# untitled.net
KiCad netlist of a schematic drawn in EAGLE
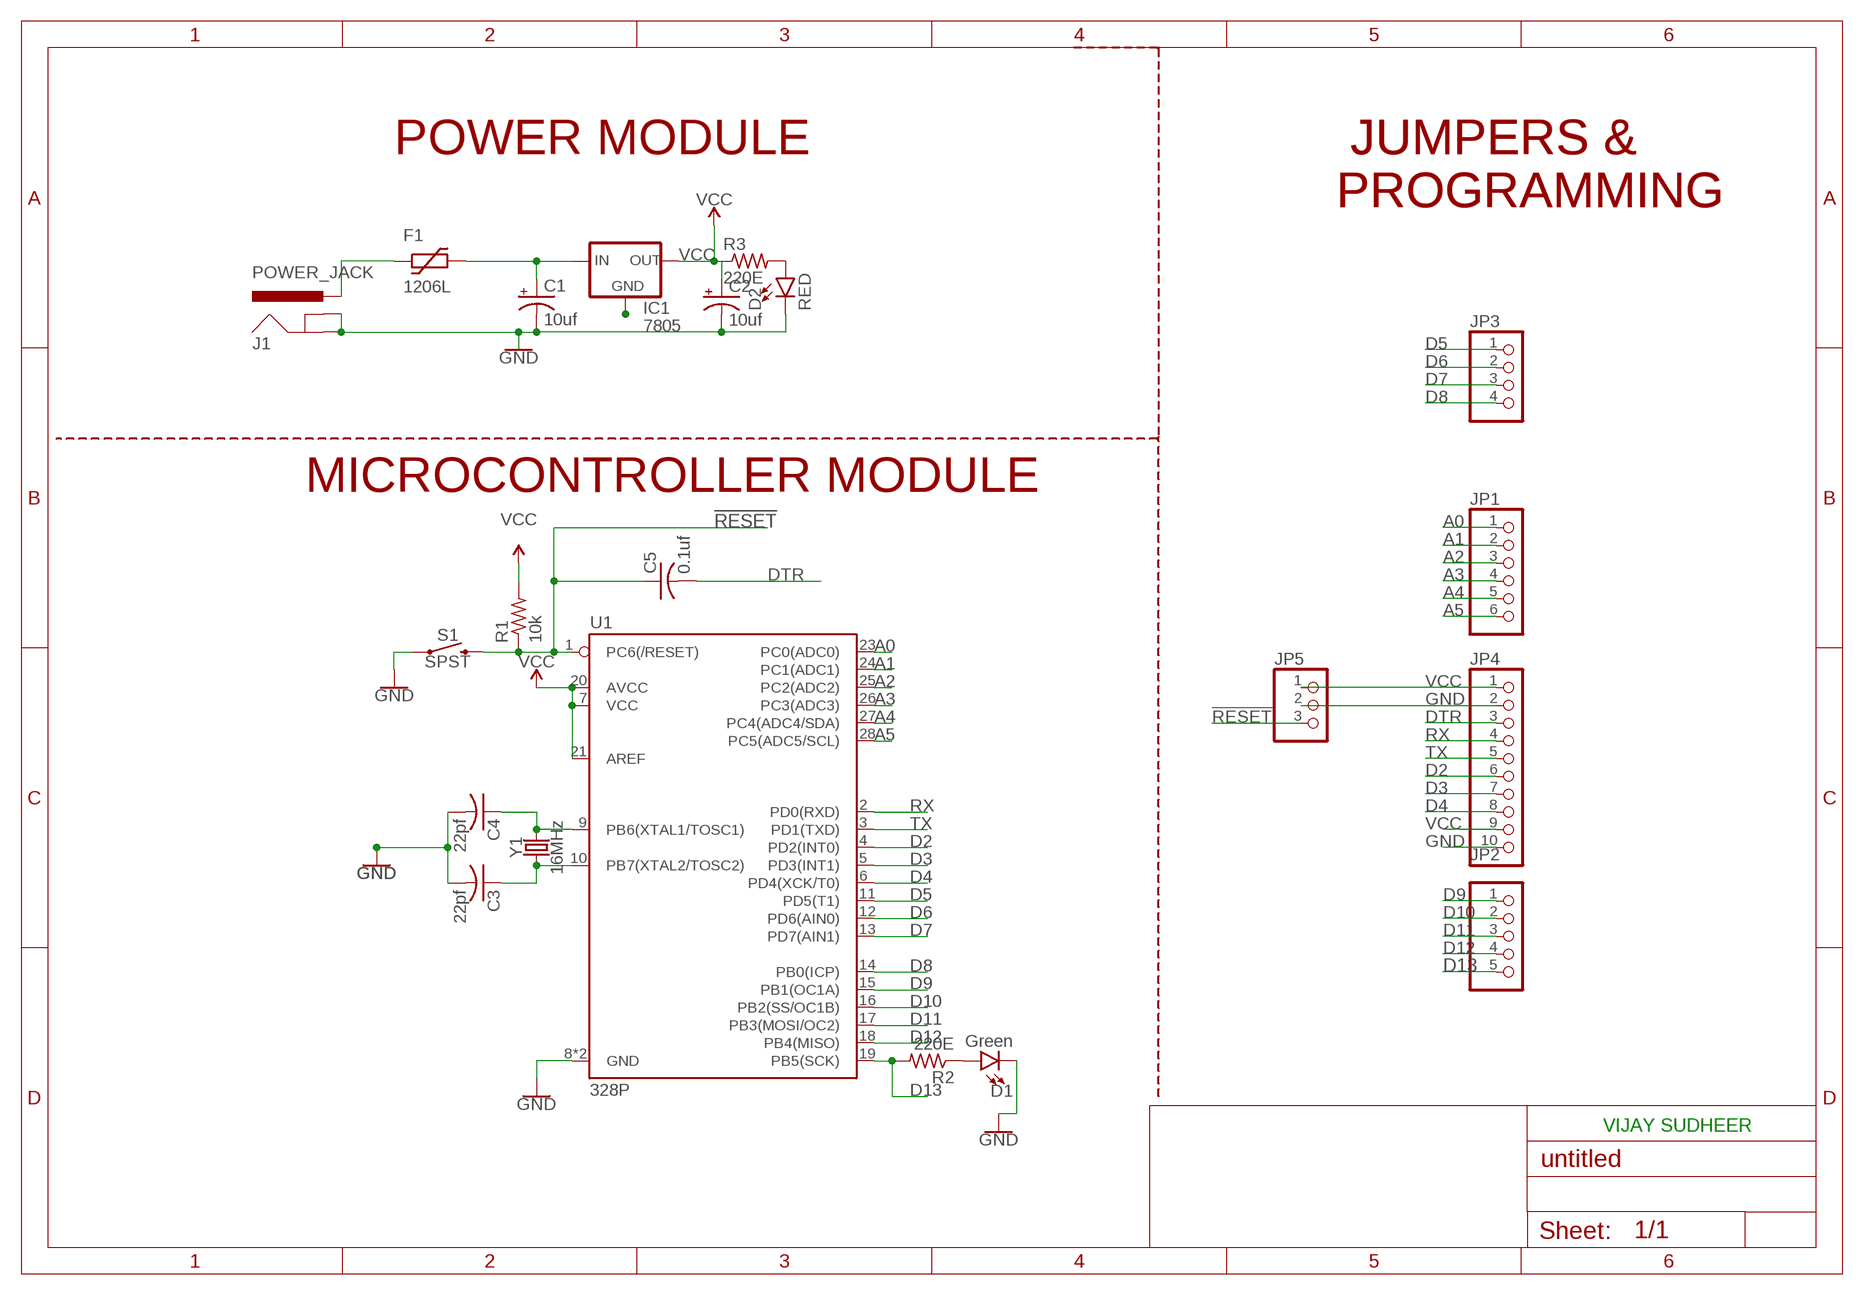
[diagram p0: schematic, sheet 1]

(export (version "E")
  (design (tool "Eeschema 10.0.6"))
  (components
    (comp (ref "C1")
      (value "10uf")
      (footprint "eagle-import:E2,5-6E")
      (libsource (lib "eagle-import") (part "CPOL-USE2,5-6E"))
    )
    (comp (ref "C2")
      (value "10uf")
      (footprint "eagle-import:E2,5-6E")
      (libsource (lib "eagle-import") (part "CPOL-USE2,5-6E"))
    )
    (comp (ref "C3")
      (value "22pf")
      (footprint "eagle-import:C025-024X044")
      (libsource (lib "eagle-import") (part "C-US025-024X044"))
    )
    (comp (ref "C4")
      (value "22pf")
      (footprint "eagle-import:C025-024X044")
      (libsource (lib "eagle-import") (part "C-US025-024X044"))
    )
    (comp (ref "C5")
      (value "0.1uf")
      (footprint "eagle-import:C025-024X044")
      (libsource (lib "eagle-import") (part "C-US025-024X044"))
    )
    (comp (ref "D1")
      (value "Green")
      (footprint "eagle-import:LED_5MM")
      (libsource (lib "eagle-import") (part "LED5MM"))
    )
    (comp (ref "D2")
      (value "RED")
      (footprint "eagle-import:LED_5MM")
      (libsource (lib "eagle-import") (part "LED5MM"))
    )
    (comp (ref "F1")
      (value "1206L")
      (footprint "eagle-import:1206L")
      (libsource (lib "eagle-import") (part "1206L"))
    )
    (comp (ref "IC1")
      (value "7805")
      (footprint "eagle-import:78XXS")
      (libsource (lib "eagle-import") (part "78XXS"))
    )
    (comp (ref "J1")
      (value "POWER_JACK")
      (footprint "eagle-import:POWER_JACK_PTH")
      (libsource (lib "eagle-import") (part "POWER_JACK"))
    )
    (comp (ref "JP1")
      (value "PINHD-1X6")
      (footprint "eagle-import:1X06")
      (libsource (lib "eagle-import") (part "PINHD-1X6"))
    )
    (comp (ref "JP2")
      (value "PINHD-1X5")
      (footprint "eagle-import:1X05")
      (libsource (lib "eagle-import") (part "PINHD-1X5"))
    )
    (comp (ref "JP3")
      (value "PINHD-1X4")
      (footprint "eagle-import:1X04")
      (libsource (lib "eagle-import") (part "PINHD-1X4"))
    )
    (comp (ref "JP4")
      (value "PINHD-1X10")
      (footprint "eagle-import:1X10")
      (libsource (lib "eagle-import") (part "PINHD-1X10"))
    )
    (comp (ref "JP5")
      (value "PINHD-1X3")
      (footprint "eagle-import:1X03")
      (libsource (lib "eagle-import") (part "PINHD-1X3"))
    )
    (comp (ref "R1")
      (value "10k")
      (footprint "eagle-import:0204_7")
      (libsource (lib "eagle-import") (part "R-US_0204/7"))
    )
    (comp (ref "R2")
      (value "220E")
      (footprint "eagle-import:0204_7")
      (libsource (lib "eagle-import") (part "R-US_0204/7"))
    )
    (comp (ref "R3")
      (value "220E")
      (footprint "eagle-import:0204_7")
      (libsource (lib "eagle-import") (part "R-US_0204/7"))
    )
    (comp (ref "S1")
      (value "SPST")
      (footprint "eagle-import:TACTILE_SWITCH_PTH_6.0MM")
      (libsource (lib "eagle-import") (part "MOMENTARY-SWITCH-SPST-PTH-6.0MM"))
    )
    (comp (ref "U1")
      (value "328P")
      (footprint "eagle-import:DIP28")
      (libsource (lib "eagle-import") (part "ATMEGA328P_PDIP"))
    )
    (comp (ref "Y1")
      (value "16MHz")
      (footprint "eagle-import:HC49US")
      (libsource (lib "eagle-import") (part "CRYSTAL-16MHZPTH-HC49US"))
    )
  )
  (nets
    (net (code "1") (name "/A0") (class "Default")
      (node (ref "JP1") (pin "1") (pinfunction "1_1") (pintype "passive"))
      (node (ref "U1") (pin "23") (pinfunction "PC0(ADC0)_23") (pintype "bidirectional"))
    )
    (net (code "2") (name "/A1") (class "Default")
      (node (ref "JP1") (pin "2") (pinfunction "2_2") (pintype "passive"))
      (node (ref "U1") (pin "24") (pinfunction "PC1(ADC1)_24") (pintype "bidirectional"))
    )
    (net (code "3") (name "/A2") (class "Default")
      (node (ref "JP1") (pin "3") (pinfunction "3_3") (pintype "passive"))
      (node (ref "U1") (pin "25") (pinfunction "PC2(ADC2)_25") (pintype "bidirectional"))
    )
    (net (code "4") (name "/A3") (class "Default")
      (node (ref "JP1") (pin "4") (pinfunction "4_4") (pintype "passive"))
      (node (ref "U1") (pin "26") (pinfunction "PC3(ADC3)_26") (pintype "bidirectional"))
    )
    (net (code "5") (name "/A4") (class "Default")
      (node (ref "JP1") (pin "5") (pinfunction "5_5") (pintype "passive"))
      (node (ref "U1") (pin "27") (pinfunction "PC4(ADC4/SDA)_27") (pintype "bidirectional"))
    )
    (net (code "6") (name "/A5") (class "Default")
      (node (ref "JP1") (pin "6") (pinfunction "6_6") (pintype "passive"))
      (node (ref "U1") (pin "28") (pinfunction "PC5(ADC5/SCL)_28") (pintype "bidirectional"))
    )
    (net (code "7") (name "/D2") (class "Default")
      (node (ref "JP4") (pin "6") (pinfunction "6_6") (pintype "passive"))
      (node (ref "U1") (pin "4") (pinfunction "PD2(INT0)_4") (pintype "bidirectional"))
    )
    (net (code "8") (name "/D3") (class "Default")
      (node (ref "JP4") (pin "7") (pinfunction "7_7") (pintype "passive"))
      (node (ref "U1") (pin "5") (pinfunction "PD3(INT1)_5") (pintype "bidirectional"))
    )
    (net (code "9") (name "/D4") (class "Default")
      (node (ref "JP4") (pin "8") (pinfunction "8_8") (pintype "passive"))
      (node (ref "U1") (pin "6") (pinfunction "PD4(XCK/T0)_6") (pintype "bidirectional"))
    )
    (net (code "10") (name "/D5") (class "Default")
      (node (ref "JP3") (pin "1") (pinfunction "1_1") (pintype "passive"))
      (node (ref "U1") (pin "11") (pinfunction "PD5(T1)_11") (pintype "bidirectional"))
    )
    (net (code "11") (name "/D6") (class "Default")
      (node (ref "JP3") (pin "2") (pinfunction "2_2") (pintype "passive"))
      (node (ref "U1") (pin "12") (pinfunction "PD6(AIN0)_12") (pintype "bidirectional"))
    )
    (net (code "12") (name "/D7") (class "Default")
      (node (ref "JP3") (pin "3") (pinfunction "3_3") (pintype "passive"))
      (node (ref "U1") (pin "13") (pinfunction "PD7(AIN1)_13") (pintype "bidirectional"))
    )
    (net (code "13") (name "/D8") (class "Default")
      (node (ref "JP3") (pin "4") (pinfunction "4_4") (pintype "passive"))
      (node (ref "U1") (pin "14") (pinfunction "PB0(ICP)_14") (pintype "bidirectional"))
    )
    (net (code "14") (name "/D9") (class "Default")
      (node (ref "JP2") (pin "1") (pinfunction "1_1") (pintype "passive"))
      (node (ref "U1") (pin "15") (pinfunction "PB1(OC1A)_15") (pintype "bidirectional"))
    )
    (net (code "15") (name "/D10") (class "Default")
      (node (ref "JP2") (pin "2") (pinfunction "2_2") (pintype "passive"))
      (node (ref "U1") (pin "16") (pinfunction "PB2(SS/OC1B)_16") (pintype "bidirectional"))
    )
    (net (code "16") (name "/D11") (class "Default")
      (node (ref "JP2") (pin "3") (pinfunction "3_3") (pintype "passive"))
      (node (ref "U1") (pin "17") (pinfunction "PB3(MOSI/OC2)_17") (pintype "bidirectional"))
    )
    (net (code "17") (name "/D12") (class "Default")
      (node (ref "JP2") (pin "4") (pinfunction "4_4") (pintype "passive"))
      (node (ref "U1") (pin "18") (pinfunction "PB4(MISO)_18") (pintype "bidirectional"))
    )
    (net (code "18") (name "/D13") (class "Default")
      (node (ref "JP2") (pin "5") (pinfunction "5_5") (pintype "passive"))
      (node (ref "R2") (pin "2") (pinfunction "2_2") (pintype "passive"))
      (node (ref "U1") (pin "19") (pinfunction "PB5(SCK)_19") (pintype "bidirectional"))
    )
    (net (code "19") (name "/DTR") (class "Default")
      (node (ref "C5") (pin "2") (pinfunction "2_2") (pintype "passive"))
      (node (ref "JP4") (pin "3") (pinfunction "3_3") (pintype "passive"))
    )
    (net (code "20") (name "/RX") (class "Default")
      (node (ref "JP4") (pin "4") (pinfunction "4_4") (pintype "passive"))
      (node (ref "U1") (pin "2") (pinfunction "PD0(RXD)_2") (pintype "bidirectional"))
    )
    (net (code "21") (name "/TX") (class "Default")
      (node (ref "JP4") (pin "5") (pinfunction "5_5") (pintype "passive"))
      (node (ref "U1") (pin "3") (pinfunction "PD1(TXD)_3") (pintype "bidirectional"))
    )
    (net (code "22") (name "/~{RESET}") (class "Default")
      (node (ref "C5") (pin "1") (pinfunction "1_1") (pintype "passive"))
      (node (ref "JP5") (pin "3") (pinfunction "3_3") (pintype "passive"))
      (node (ref "R1") (pin "1") (pinfunction "1_1") (pintype "passive"))
      (node (ref "S1") (pin "3") (pinfunction "2_3") (pintype "passive"))
      (node (ref "U1") (pin "1") (pinfunction "PC6(/RESET)_1") (pintype "bidirectional"))
    )
    (net (code "23") (name "GND") (class "Default")
      (node (ref "C1") (pin "-") (pinfunction "-_-") (pintype "passive"))
      (node (ref "C2") (pin "-") (pinfunction "-_-") (pintype "passive"))
      (node (ref "C3") (pin "2") (pinfunction "2_2") (pintype "passive"))
      (node (ref "C4") (pin "2") (pinfunction "2_2") (pintype "passive"))
      (node (ref "D1") (pin "K") (pinfunction "C_K") (pintype "passive"))
      (node (ref "D2") (pin "K") (pinfunction "C_K") (pintype "passive"))
      (node (ref "J1") (pin "GND") (pinfunction "GND_GND") (pintype "bidirectional"))
      (node (ref "J1") (pin "GNDBREAK") (pinfunction "GNDBREAK_GNDBREAK") (pintype "bidirectional"))
      (node (ref "JP4") (pin "10") (pinfunction "10_10") (pintype "passive"))
      (node (ref "JP4") (pin "2") (pinfunction "2_2") (pintype "passive"))
      (node (ref "JP5") (pin "2") (pinfunction "2_2") (pintype "passive"))
      (node (ref "S1") (pin "1") (pinfunction "1_1") (pintype "passive"))
      (node (ref "U1") (pin "22") (pinfunction "GND_22") (pintype "bidirectional"))
      (node (ref "U1") (pin "8") (pinfunction "GND_8") (pintype "bidirectional"))
    )
    (net (code "24") (name "Net-(D1-PadA)") (class "Default")
      (node (ref "D1") (pin "A") (pinfunction "A_A") (pintype "passive"))
      (node (ref "R2") (pin "1") (pinfunction "1_1") (pintype "passive"))
    )
    (net (code "25") (name "Net-(D2-PadA)") (class "Default")
      (node (ref "D2") (pin "A") (pinfunction "A_A") (pintype "passive"))
      (node (ref "R3") (pin "2") (pinfunction "2_2") (pintype "passive"))
    )
    (net (code "26") (name "Net-(F1-1)") (class "Default")
      (node (ref "F1") (pin "P$1") (pinfunction "1_P$1") (pintype "passive"))
      (node (ref "J1") (pin "PWR") (pinfunction "PWR_PWR") (pintype "bidirectional"))
    )
    (net (code "27") (name "Net-(F1-2)") (class "Default")
      (node (ref "C1") (pin "+") (pinfunction "+_+") (pintype "passive"))
      (node (ref "F1") (pin "P$2") (pinfunction "2_P$2") (pintype "passive"))
      (node (ref "IC1") (pin "IN") (pinfunction "IN_IN") (pintype "input"))
    )
    (net (code "28") (name "Net-(U1-PB6(XTAL1{slash}TOSC1))") (class "Default")
      (node (ref "C4") (pin "1") (pinfunction "1_1") (pintype "passive"))
      (node (ref "U1") (pin "9") (pinfunction "PB6(XTAL1/TOSC1)_9") (pintype "bidirectional"))
      (node (ref "Y1") (pin "2") (pinfunction "2_2") (pintype "passive"))
    )
    (net (code "29") (name "Net-(U1-PB7(XTAL2{slash}TOSC2))") (class "Default")
      (node (ref "C3") (pin "1") (pinfunction "1_1") (pintype "passive"))
      (node (ref "U1") (pin "10") (pinfunction "PB7(XTAL2/TOSC2)_10") (pintype "bidirectional"))
      (node (ref "Y1") (pin "1") (pinfunction "1_1") (pintype "passive"))
    )
    (net (code "30") (name "VCC") (class "Default")
      (node (ref "C2") (pin "+") (pinfunction "+_+") (pintype "passive"))
      (node (ref "IC1") (pin "OUT") (pinfunction "OUT_OUT") (pintype "passive"))
      (node (ref "JP4") (pin "1") (pinfunction "1_1") (pintype "passive"))
      (node (ref "JP4") (pin "9") (pinfunction "9_9") (pintype "passive"))
      (node (ref "JP5") (pin "1") (pinfunction "1_1") (pintype "passive"))
      (node (ref "R1") (pin "2") (pinfunction "2_2") (pintype "passive"))
      (node (ref "R3") (pin "1") (pinfunction "1_1") (pintype "passive"))
      (node (ref "U1") (pin "20") (pinfunction "AVCC_20") (pintype "bidirectional"))
      (node (ref "U1") (pin "21") (pinfunction "AREF_21") (pintype "bidirectional"))
      (node (ref "U1") (pin "7") (pinfunction "VCC_7") (pintype "bidirectional"))
    )
    (net (code "31") (name "unconnected-(IC1-PadGND)") (class "Default")
      (node (ref "IC1") (pin "GND") (pinfunction "GND_GND") (pintype "input"))
    )
  )
)
